# SkyWindow_SCH.net
KiCad netlist of a schematic drawn in Altium Designer
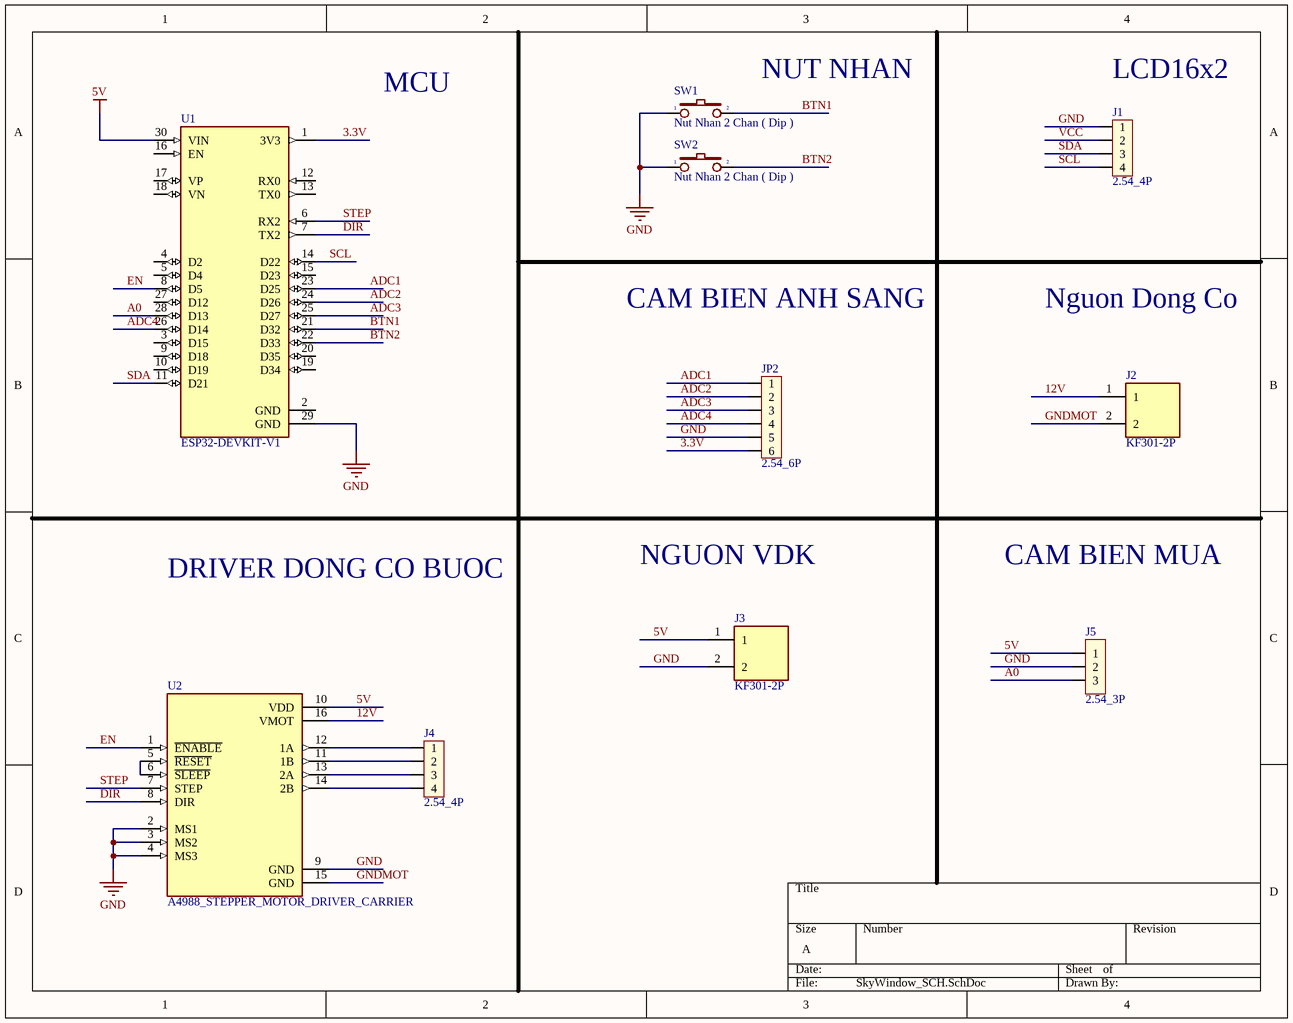
[diagram p0: SkyWindow_SCH.SchDoc]

(export (version "E")
  (design (tool "Eeschema 10.0.6"))
  (components
    (comp (ref "J1")
      (value "2.54_4P")
      (footprint "JP4")
      (description "Cắm")
      (libsource (lib "THU VIEN SCH") (part "Jum Don Duc 2.54_4P"))
    )
    (comp (ref "J2")
      (value "KF301-2P")
      (footprint "HANDSON_KF301-2P")
      (description "2 Pin Terminal Block 5mm Pitch")
      (libsource (lib "KF301-2P") (part "KF301-2P"))
    )
    (comp (ref "J3")
      (value "KF301-2P")
      (footprint "HANDSON_KF301-2P")
      (description "2 Pin Terminal Block 5mm Pitch")
      (libsource (lib "KF301-2P") (part "KF301-2P"))
    )
    (comp (ref "J4")
      (value "2.54_4P")
      (footprint "JP4")
      (description "Cắm")
      (libsource (lib "THU VIEN SCH") (part "Jum Don Duc 2.54_4P"))
    )
    (comp (ref "J5")
      (value "2.54_3P")
      (footprint "JP3")
      (description "Cắm")
      (libsource (lib "THU VIEN SCH") (part "Jum Don Duc 2.54_3P"))
    )
    (comp (ref "JP2")
      (value "2.54_6P")
      (footprint "JP6")
      (description "Cắm")
      (libsource (lib "THU VIEN SCH") (part "Jum Don Duc 2.54_6P"))
    )
    (comp (ref "SW1")
      (value "Nut Nhan 2 Chan ( Dip )")
      (footprint "SW2")
      (description "Cắm")
      (libsource (lib "THU VIEN SCH") (part "Nut Nhan 2 Chan ( Dip )"))
    )
    (comp (ref "SW2")
      (value "Nut Nhan 2 Chan ( Dip )")
      (footprint "SW2")
      (description "Cắm")
      (libsource (lib "THU VIEN SCH") (part "Nut Nhan 2 Chan ( Dip )"))
    )
    (comp (ref "U1")
      (value "ESP32-DEVKIT-V1")
      (footprint "MODULE_ESP32_DEVKIT_V1")
      (fields (field (name "MF") "Do it"))
      (libsource (lib "ESP32-DEVKIT-V1") (part "ESP32-DEVKIT-V1"))
    )
    (comp (ref "U2")
      (value "A4988_STEPPER_MOTOR_DRIVER_CARRIER")
      (footprint "MODULE_A4988_STEPPER_MOTOR_DRIVER_CARRIER")
      (description "Stepper motor controler; IC: A4988; 1A; Uin mot: 8Ã·35V")
      (libsource (lib "A4988_STEPPER_MOTOR_DRIVER_CARRIER") (part "A4988_STEPPER_MOTOR_DRIVER_CARRIER"))
    )
  )
  (nets
    (net (code "1") (name "/3.3V") (class "Default")
      (node (ref "JP2") (pin "6") (pinfunction "6_6") (pintype "passive"))
      (node (ref "U1") (pin "1") (pinfunction "3V3_1") (pintype "output"))
    )
    (net (code "2") (name "/12V") (class "Default")
      (node (ref "J2") (pin "1") (pinfunction "1_1") (pintype "passive"))
      (node (ref "U2") (pin "16") (pinfunction "VMOT_16") (pintype "power_in"))
    )
    (net (code "3") (name "/A0") (class "Default")
      (node (ref "J5") (pin "3") (pinfunction "3_3") (pintype "passive"))
      (node (ref "U1") (pin "28") (pinfunction "D13_28") (pintype "bidirectional"))
    )
    (net (code "4") (name "/ADC1") (class "Default")
      (node (ref "JP2") (pin "1") (pinfunction "1_1") (pintype "passive"))
      (node (ref "U1") (pin "23") (pinfunction "D25_23") (pintype "bidirectional"))
    )
    (net (code "5") (name "/ADC2") (class "Default")
      (node (ref "JP2") (pin "2") (pinfunction "2_2") (pintype "passive"))
      (node (ref "U1") (pin "24") (pinfunction "D26_24") (pintype "bidirectional"))
    )
    (net (code "6") (name "/ADC3") (class "Default")
      (node (ref "JP2") (pin "3") (pinfunction "3_3") (pintype "passive"))
      (node (ref "U1") (pin "25") (pinfunction "D27_25") (pintype "bidirectional"))
    )
    (net (code "7") (name "/ADC4") (class "Default")
      (node (ref "JP2") (pin "4") (pinfunction "4_4") (pintype "passive"))
      (node (ref "U1") (pin "26") (pinfunction "D14_26") (pintype "bidirectional"))
    )
    (net (code "8") (name "/BTN1") (class "Default")
      (node (ref "SW1") (pin "2") (pinfunction "2_2") (pintype "passive"))
      (node (ref "U1") (pin "21") (pinfunction "D32_21") (pintype "bidirectional"))
    )
    (net (code "9") (name "/BTN2") (class "Default")
      (node (ref "SW2") (pin "2") (pinfunction "2_2") (pintype "passive"))
      (node (ref "U1") (pin "22") (pinfunction "D33_22") (pintype "bidirectional"))
    )
    (net (code "10") (name "/DIR") (class "Default")
      (node (ref "U1") (pin "7") (pinfunction "TX2_7") (pintype "output"))
      (node (ref "U2") (pin "8") (pinfunction "DIR_8") (pintype "input"))
    )
    (net (code "11") (name "/EN") (class "Default")
      (node (ref "U1") (pin "8") (pinfunction "D5_8") (pintype "bidirectional"))
      (node (ref "U2") (pin "1") (pinfunction "~{ENABLE}_1") (pintype "input"))
    )
    (net (code "12") (name "/GNDMOT") (class "Default")
      (node (ref "J2") (pin "2") (pinfunction "2_2") (pintype "passive"))
      (node (ref "U2") (pin "15") (pinfunction "GND_15") (pintype "power_in"))
    )
    (net (code "13") (name "/SCL") (class "Default")
      (node (ref "J1") (pin "4") (pinfunction "4_4") (pintype "passive"))
      (node (ref "U1") (pin "14") (pinfunction "D22_14") (pintype "bidirectional"))
    )
    (net (code "14") (name "/SDA") (class "Default")
      (node (ref "J1") (pin "3") (pinfunction "3_3") (pintype "passive"))
      (node (ref "U1") (pin "11") (pinfunction "D21_11") (pintype "bidirectional"))
    )
    (net (code "15") (name "/STEP") (class "Default")
      (node (ref "U1") (pin "6") (pinfunction "RX2_6") (pintype "input"))
      (node (ref "U2") (pin "7") (pinfunction "STEP_7") (pintype "input"))
    )
    (net (code "16") (name "/VCC") (class "Default")
      (node (ref "J1") (pin "2") (pinfunction "2_2") (pintype "passive"))
    )
    (net (code "17") (name "5V") (class "Default")
      (node (ref "J3") (pin "1") (pinfunction "1_1") (pintype "passive"))
      (node (ref "J5") (pin "1") (pinfunction "1_1") (pintype "passive"))
      (node (ref "U1") (pin "30") (pinfunction "VIN_30") (pintype "input"))
      (node (ref "U2") (pin "10") (pinfunction "VDD_10") (pintype "power_in"))
    )
    (net (code "18") (name "GND") (class "Default")
      (node (ref "J1") (pin "1") (pinfunction "1_1") (pintype "passive"))
      (node (ref "J3") (pin "2") (pinfunction "2_2") (pintype "passive"))
      (node (ref "J5") (pin "2") (pinfunction "2_2") (pintype "passive"))
      (node (ref "JP2") (pin "5") (pinfunction "5_5") (pintype "passive"))
      (node (ref "SW1") (pin "1") (pinfunction "1_1") (pintype "passive"))
      (node (ref "SW2") (pin "1") (pinfunction "1_1") (pintype "passive"))
      (node (ref "U1") (pin "29") (pinfunction "GND_29") (pintype "power_in"))
      (node (ref "U2") (pin "2") (pinfunction "MS1_2") (pintype "input"))
      (node (ref "U2") (pin "3") (pinfunction "MS2_3") (pintype "input"))
      (node (ref "U2") (pin "4") (pinfunction "MS3_4") (pintype "input"))
      (node (ref "U2") (pin "9") (pinfunction "GND_9") (pintype "power_in"))
    )
    (net (code "19") (name "Net-(U2-1A)") (class "Default")
      (node (ref "J4") (pin "1") (pinfunction "1_1") (pintype "passive"))
      (node (ref "U2") (pin "12") (pinfunction "1A_12") (pintype "output"))
    )
    (net (code "20") (name "Net-(U2-1B)") (class "Default")
      (node (ref "J4") (pin "2") (pinfunction "2_2") (pintype "passive"))
      (node (ref "U2") (pin "11") (pinfunction "1B_11") (pintype "output"))
    )
    (net (code "21") (name "Net-(U2-2A)") (class "Default")
      (node (ref "J4") (pin "3") (pinfunction "3_3") (pintype "passive"))
      (node (ref "U2") (pin "13") (pinfunction "2A_13") (pintype "output"))
    )
    (net (code "22") (name "Net-(U2-2B)") (class "Default")
      (node (ref "J4") (pin "4") (pinfunction "4_4") (pintype "passive"))
      (node (ref "U2") (pin "14") (pinfunction "2B_14") (pintype "output"))
    )
    (net (code "23") (name "Net-(U2-~{RESET})") (class "Default")
      (node (ref "U2") (pin "5") (pinfunction "~{RESET}_5") (pintype "input"))
      (node (ref "U2") (pin "6") (pinfunction "~{SLEEP}_6") (pintype "input"))
    )
    (net (code "24") (name "unconnected-(U1-D2-Pad4)") (class "Default")
      (node (ref "U1") (pin "4") (pinfunction "D2_4") (pintype "bidirectional"))
    )
    (net (code "25") (name "unconnected-(U1-D4-Pad5)") (class "Default")
      (node (ref "U1") (pin "5") (pinfunction "D4_5") (pintype "bidirectional"))
    )
    (net (code "26") (name "unconnected-(U1-D12-Pad27)") (class "Default")
      (node (ref "U1") (pin "27") (pinfunction "D12_27") (pintype "bidirectional"))
    )
    (net (code "27") (name "unconnected-(U1-D15-Pad3)") (class "Default")
      (node (ref "U1") (pin "3") (pinfunction "D15_3") (pintype "bidirectional"))
    )
    (net (code "28") (name "unconnected-(U1-D18-Pad9)") (class "Default")
      (node (ref "U1") (pin "9") (pinfunction "D18_9") (pintype "bidirectional"))
    )
    (net (code "29") (name "unconnected-(U1-D19-Pad10)") (class "Default")
      (node (ref "U1") (pin "10") (pinfunction "D19_10") (pintype "bidirectional"))
    )
    (net (code "30") (name "unconnected-(U1-D23-Pad15)") (class "Default")
      (node (ref "U1") (pin "15") (pinfunction "D23_15") (pintype "bidirectional"))
    )
    (net (code "31") (name "unconnected-(U1-D34-Pad19)") (class "Default")
      (node (ref "U1") (pin "19") (pinfunction "D34_19") (pintype "bidirectional"))
    )
    (net (code "32") (name "unconnected-(U1-D35-Pad20)") (class "Default")
      (node (ref "U1") (pin "20") (pinfunction "D35_20") (pintype "bidirectional"))
    )
    (net (code "33") (name "unconnected-(U1-EN-Pad16)") (class "Default")
      (node (ref "U1") (pin "16") (pinfunction "EN_16") (pintype "input"))
    )
    (net (code "34") (name "unconnected-(U1-GND-Pad2)") (class "Default")
      (node (ref "U1") (pin "2") (pinfunction "GND_2") (pintype "power_in"))
    )
    (net (code "35") (name "unconnected-(U1-RX0-Pad12)") (class "Default")
      (node (ref "U1") (pin "12") (pinfunction "RX0_12") (pintype "input"))
    )
    (net (code "36") (name "unconnected-(U1-TX0-Pad13)") (class "Default")
      (node (ref "U1") (pin "13") (pinfunction "TX0_13") (pintype "output"))
    )
    (net (code "37") (name "unconnected-(U1-VN-Pad18)") (class "Default")
      (node (ref "U1") (pin "18") (pinfunction "VN_18") (pintype "bidirectional"))
    )
    (net (code "38") (name "unconnected-(U1-VP-Pad17)") (class "Default")
      (node (ref "U1") (pin "17") (pinfunction "VP_17") (pintype "bidirectional"))
    )
  )
)
